# Ultrasonic_Transmitter.net
KiCad netlist of a schematic drawn in Altium Designer
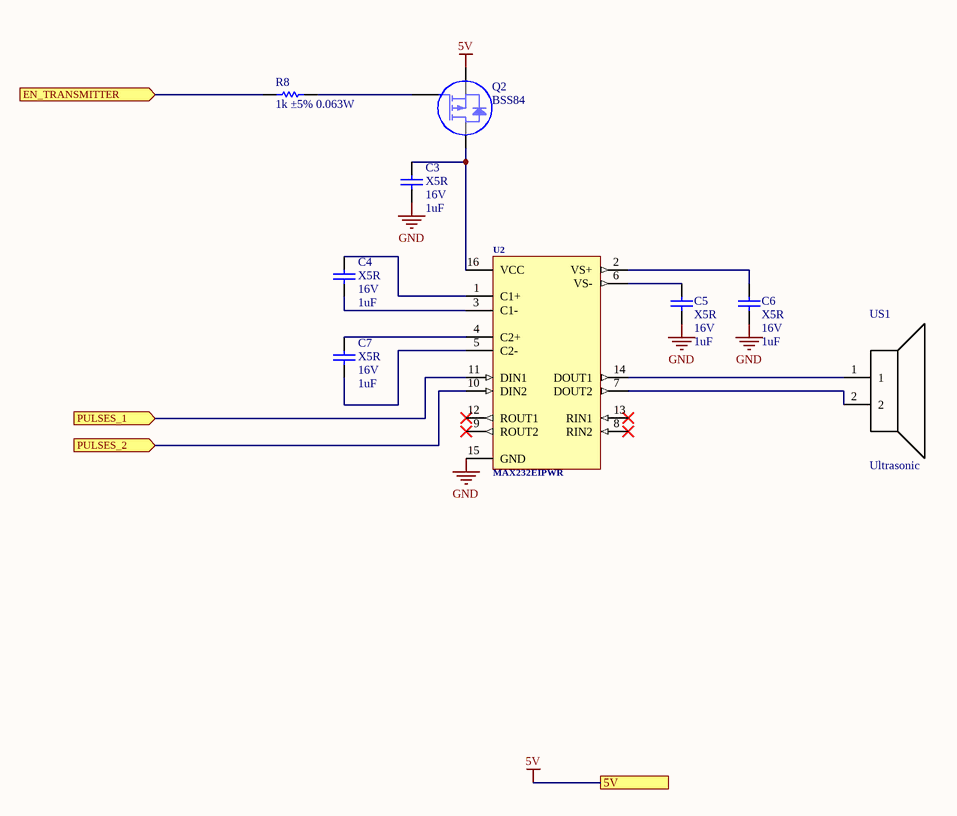
[diagram p0: Ultrasonic_Transmitter.SchDoc]

(export (version "E")
  (design (tool "Eeschema 10.0.6"))
  (components
    (comp (ref "C3")
      (value "Capacitor")
      (footprint "C0603")
      (description "Capacitor SMD")
      (fields
        (field (name "DIELECTRIC") "X5R")
        (field (name "VOLTAGE") "16V")
        (field (name "CAPACITANCE") "1uF")
        (field (name "PART NUMBER") "C0603_1uF_16V_±10%")
        (field (name "TOLERANCE") "±10%")
      )
      (libsource (lib "Pasives_Capacitor_SMD") (part "Capacitor"))
    )
    (comp (ref "C4")
      (value "Capacitor")
      (footprint "C0603")
      (description "Capacitor SMD")
      (fields
        (field (name "DIELECTRIC") "X5R")
        (field (name "VOLTAGE") "16V")
        (field (name "CAPACITANCE") "1uF")
        (field (name "PART NUMBER") "C0603_1uF_16V_±10%")
        (field (name "TOLERANCE") "±10%")
      )
      (libsource (lib "Pasives_Capacitor_SMD") (part "Capacitor"))
    )
    (comp (ref "C5")
      (value "Capacitor")
      (footprint "C0603")
      (description "Capacitor SMD")
      (fields
        (field (name "DIELECTRIC") "X5R")
        (field (name "VOLTAGE") "16V")
        (field (name "CAPACITANCE") "1uF")
        (field (name "PART NUMBER") "C0603_1uF_16V_±10%")
        (field (name "TOLERANCE") "±10%")
      )
      (libsource (lib "Pasives_Capacitor_SMD") (part "Capacitor"))
    )
    (comp (ref "C6")
      (value "Capacitor")
      (footprint "C0603")
      (description "Capacitor SMD")
      (fields
        (field (name "DIELECTRIC") "X5R")
        (field (name "VOLTAGE") "16V")
        (field (name "CAPACITANCE") "1uF")
        (field (name "PART NUMBER") "C0603_1uF_16V_±10%")
        (field (name "TOLERANCE") "±10%")
      )
      (libsource (lib "Pasives_Capacitor_SMD") (part "Capacitor"))
    )
    (comp (ref "C7")
      (value "Capacitor")
      (footprint "C0603")
      (description "Capacitor SMD")
      (fields
        (field (name "DIELECTRIC") "X5R")
        (field (name "VOLTAGE") "16V")
        (field (name "CAPACITANCE") "1uF")
        (field (name "PART NUMBER") "C0603_1uF_16V_±10%")
        (field (name "TOLERANCE") "±10%")
      )
      (libsource (lib "Pasives_Capacitor_SMD") (part "Capacitor"))
    )
    (comp (ref "Q2")
      (value "BSS84")
      (footprint "SOT23-3")
      (description "PFET")
      (fields (field (name "MANUFACTURER") "Fairchild Semiconductor"))
      (libsource (lib "Semiconductors_Transistors") (part "Mosfet_P"))
    )
    (comp (ref "R8")
      (value "1k ±5% 0.063W")
      (footprint "R0402")
      (description "Resistor, SMD")
      (fields (field (name "TOLERANCE") "±5%") (field (name "POWER") "0.063W"))
      (libsource (lib "Pasives_Resistor_SMD") (part "Resistor"))
    )
    (comp (ref "U2")
      (value "MAX232EIPWR")
      (footprint "TSSOP16")
      (description "Dual RS-232 Driver/Receiver")
      (fields (field (name "MANUFACTURER") "Texas Instruments"))
      (libsource (lib "Transceiver") (part "MAX232EIPWR"))
    )
    (comp (ref "US1")
      (value "Ultrasonic")
      (footprint "NU40C16")
      (description "Ultrasonic Sensor")
      (fields (field (name "PART NUMBER") "NU40C16T-2") (field (name "MANUFACTURER") "Jinci"))
      (libsource (lib "Sensors") (part "Ultrasonic"))
    )
  )
  (nets
    (net (code "1") (name "/EN_TRANSMITTER") (class "Default")
      (node (ref "R8") (pin "1") (pinfunction "1_1") (pintype "passive"))
    )
    (net (code "2") (name "/PULSES_1") (class "Default")
      (node (ref "U2") (pin "11") (pinfunction "DIN1_11") (pintype "input"))
    )
    (net (code "3") (name "/PULSES_2") (class "Default")
      (node (ref "U2") (pin "10") (pinfunction "DIN2_10") (pintype "input"))
    )
    (net (code "4") (name "5V") (class "Default")
      (node (ref "Q2") (pin "2") (pinfunction "S_2") (pintype "passive"))
    )
    (net (code "5") (name "GND") (class "Default")
      (node (ref "C3") (pin "1") (pinfunction "1_1") (pintype "passive"))
      (node (ref "C5") (pin "1") (pinfunction "1_1") (pintype "passive"))
      (node (ref "C6") (pin "1") (pinfunction "1_1") (pintype "passive"))
      (node (ref "U2") (pin "15") (pinfunction "GND_15") (pintype "power_in"))
    )
    (net (code "6") (name "Net-(Q2-D)") (class "Default")
      (node (ref "C3") (pin "2") (pinfunction "2_2") (pintype "passive"))
      (node (ref "Q2") (pin "3") (pinfunction "D_3") (pintype "passive"))
      (node (ref "U2") (pin "16") (pinfunction "VCC_16") (pintype "power_in"))
    )
    (net (code "7") (name "Net-(Q2-G)") (class "Default")
      (node (ref "Q2") (pin "1") (pinfunction "G_1") (pintype "passive"))
      (node (ref "R8") (pin "2") (pinfunction "2_2") (pintype "passive"))
    )
    (net (code "8") (name "Net-(U2-C1+)") (class "Default")
      (node (ref "C4") (pin "2") (pinfunction "2_2") (pintype "passive"))
      (node (ref "U2") (pin "1") (pinfunction "C1+_1") (pintype "passive"))
    )
    (net (code "9") (name "Net-(U2-C1-)") (class "Default")
      (node (ref "C4") (pin "1") (pinfunction "1_1") (pintype "passive"))
      (node (ref "U2") (pin "3") (pinfunction "C1-_3") (pintype "passive"))
    )
    (net (code "10") (name "Net-(U2-C2+)") (class "Default")
      (node (ref "C7") (pin "2") (pinfunction "2_2") (pintype "passive"))
      (node (ref "U2") (pin "4") (pinfunction "C2+_4") (pintype "passive"))
    )
    (net (code "11") (name "Net-(U2-C2-)") (class "Default")
      (node (ref "C7") (pin "1") (pinfunction "1_1") (pintype "passive"))
      (node (ref "U2") (pin "5") (pinfunction "C2-_5") (pintype "passive"))
    )
    (net (code "12") (name "Net-(U2-DOUT1)") (class "Default")
      (node (ref "U2") (pin "14") (pinfunction "DOUT1_14") (pintype "output"))
      (node (ref "US1") (pin "1") (pinfunction "1_1") (pintype "passive"))
    )
    (net (code "13") (name "Net-(U2-DOUT2)") (class "Default")
      (node (ref "U2") (pin "7") (pinfunction "DOUT2_7") (pintype "output"))
      (node (ref "US1") (pin "2") (pinfunction "2_2") (pintype "passive"))
    )
    (net (code "14") (name "Net-(U2-VS+)") (class "Default")
      (node (ref "C6") (pin "2") (pinfunction "2_2") (pintype "passive"))
      (node (ref "U2") (pin "2") (pinfunction "VS+_2") (pintype "output"))
    )
    (net (code "15") (name "Net-(U2-VS-)") (class "Default")
      (node (ref "C5") (pin "2") (pinfunction "2_2") (pintype "passive"))
      (node (ref "U2") (pin "6") (pinfunction "VS-_6") (pintype "output"))
    )
    (net (code "16") (name "unconnected-(U2-RIN1-Pad13)") (class "Default")
      (node (ref "U2") (pin "13") (pinfunction "RIN1_13") (pintype "input+no_connect"))
    )
    (net (code "17") (name "unconnected-(U2-RIN2-Pad8)") (class "Default")
      (node (ref "U2") (pin "8") (pinfunction "RIN2_8") (pintype "input+no_connect"))
    )
    (net (code "18") (name "unconnected-(U2-ROUT1-Pad12)") (class "Default")
      (node (ref "U2") (pin "12") (pinfunction "ROUT1_12") (pintype "output+no_connect"))
    )
    (net (code "19") (name "unconnected-(U2-ROUT2-Pad9)") (class "Default")
      (node (ref "U2") (pin "9") (pinfunction "ROUT2_9") (pintype "output+no_connect"))
    )
  )
)
